# FubarinoMini_v11.net
KiCad netlist of a schematic drawn in EAGLE
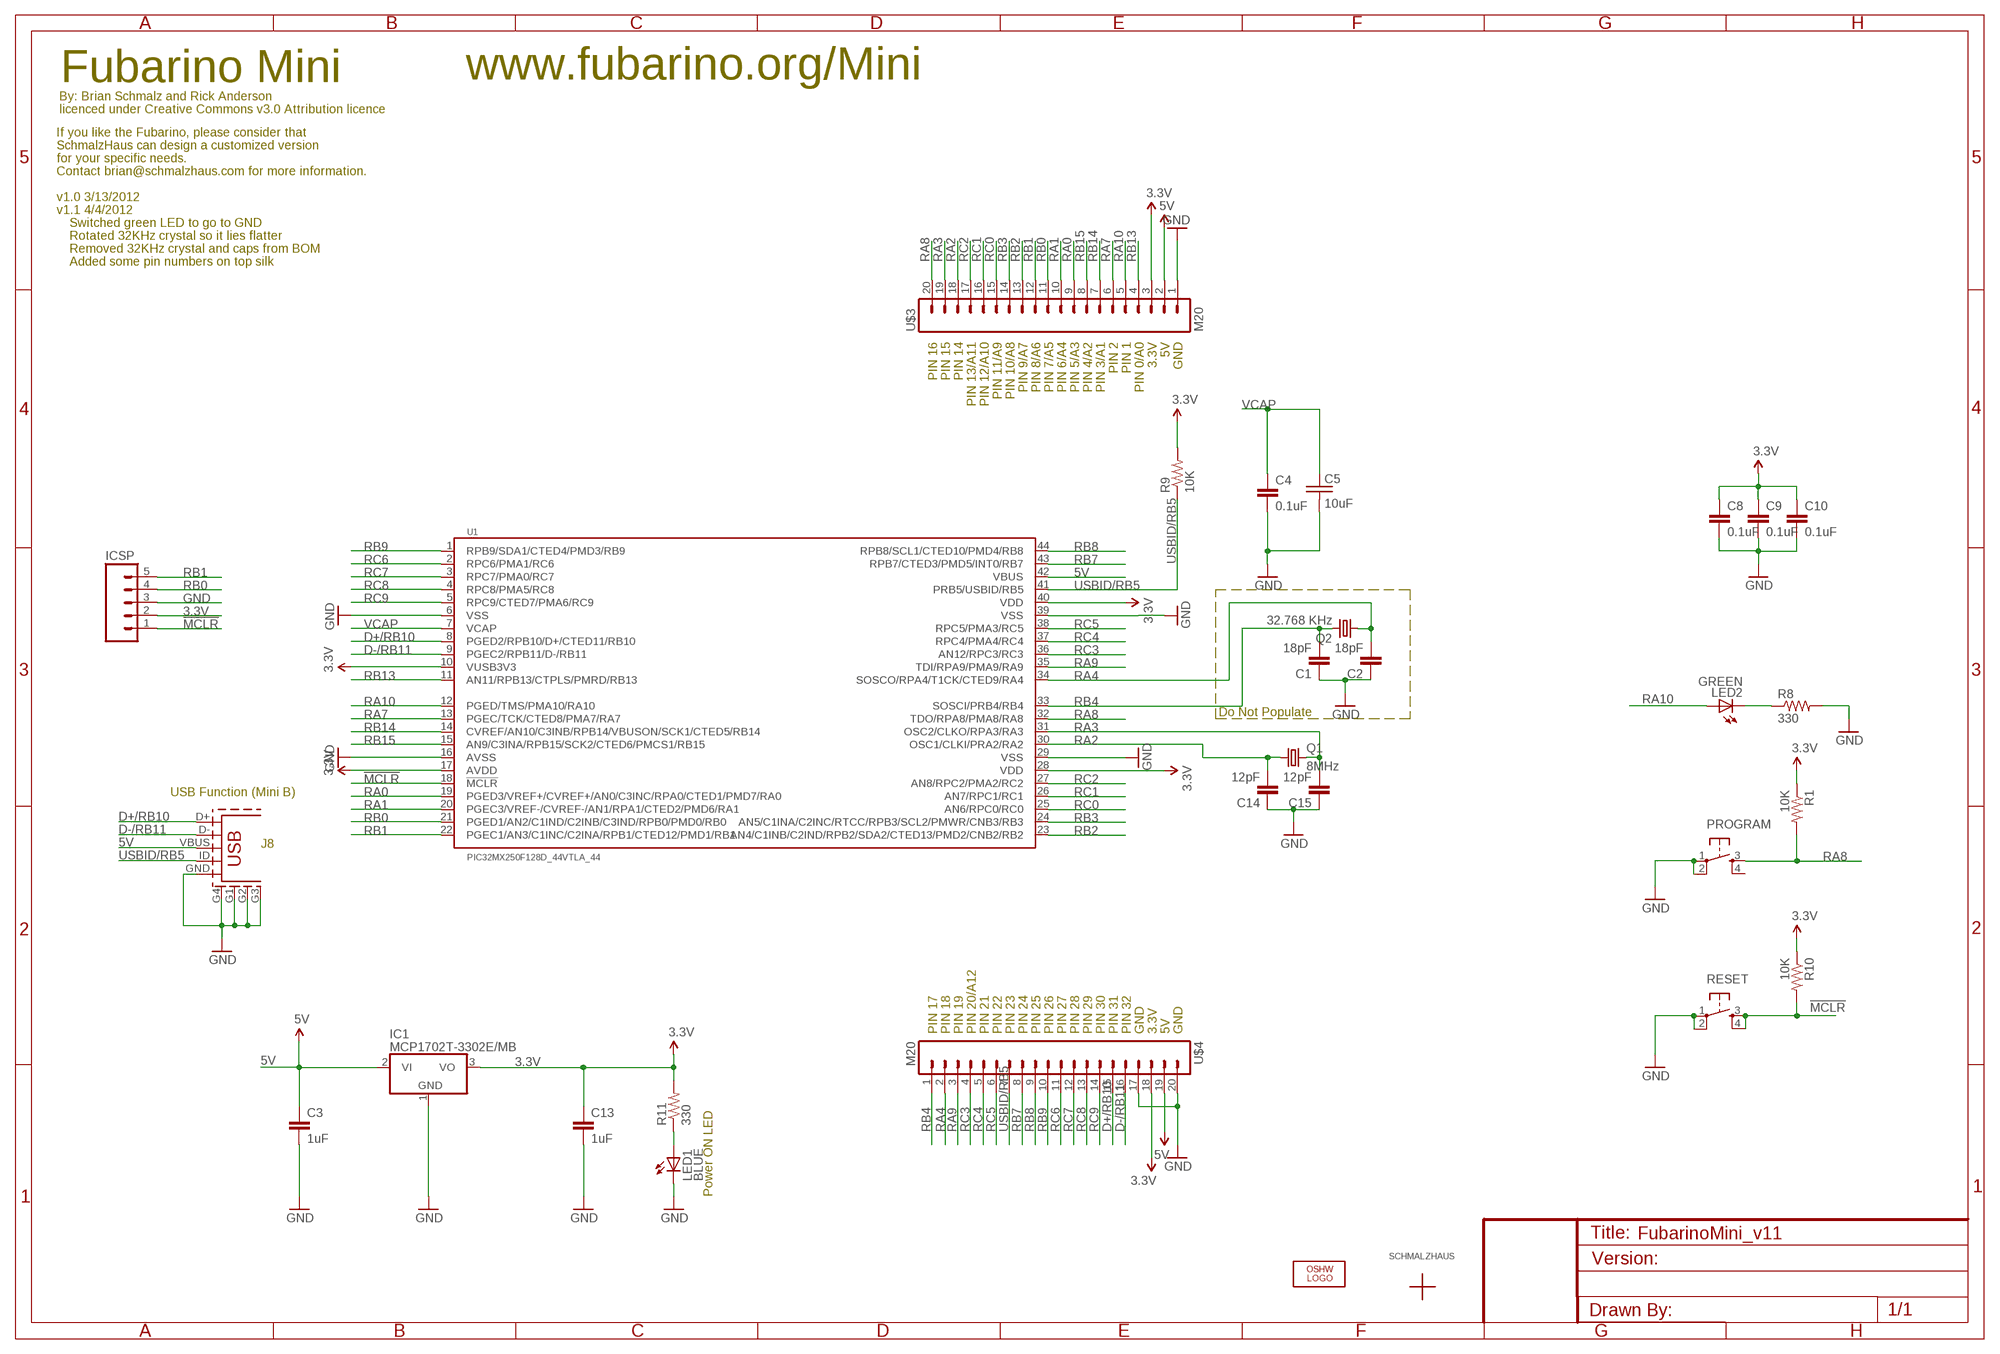
[diagram p0: schematic, sheet 1]

(export (version "E")
  (design (tool "Eeschema 10.0.6"))
  (components
    (comp (ref "C1")
      (value "18pF")
      (footprint "eagle-import:0603-CAP")
      (libsource (lib "eagle-import") (part "CAP0603-CAP"))
    )
    (comp (ref "C2")
      (value "18pF")
      (footprint "eagle-import:0603-CAP")
      (libsource (lib "eagle-import") (part "CAP0603-CAP"))
    )
    (comp (ref "C3")
      (value "1uF")
      (footprint "eagle-import:0603-CAP")
      (libsource (lib "eagle-import") (part "CAP0603-CAP"))
    )
    (comp (ref "C4")
      (value "0.1uF")
      (footprint "eagle-import:0603-CAP")
      (libsource (lib "eagle-import") (part "CAP0603-CAP"))
    )
    (comp (ref "C5")
      (value "10uF")
      (footprint "eagle-import:CAP_0805")
      (libsource (lib "eagle-import") (part "CAP0805"))
    )
    (comp (ref "C8")
      (value "0.1uF")
      (footprint "eagle-import:0603-CAP")
      (libsource (lib "eagle-import") (part "CAP0603-CAP"))
    )
    (comp (ref "C9")
      (value "0.1uF")
      (footprint "eagle-import:0603-CAP")
      (libsource (lib "eagle-import") (part "CAP0603-CAP"))
    )
    (comp (ref "C10")
      (value "0.1uF")
      (footprint "eagle-import:0603")
      (libsource (lib "eagle-import") (part "CAP0603"))
    )
    (comp (ref "C13")
      (value "1uF")
      (footprint "eagle-import:0603")
      (libsource (lib "eagle-import") (part "CAP0603"))
    )
    (comp (ref "C14")
      (value "12pF")
      (footprint "eagle-import:0603-CAP")
      (libsource (lib "eagle-import") (part "CAP0603-CAP"))
    )
    (comp (ref "C15")
      (value "12pF")
      (footprint "eagle-import:0603-CAP")
      (libsource (lib "eagle-import") (part "CAP0603-CAP"))
    )
    (comp (ref "IC1")
      (value "MCP1702T-3302E/MB")
      (footprint "eagle-import:SOT89")
      (libsource (lib "eagle-import") (part "MCP1703MB33"))
    )
    (comp (ref "ICSP")
      (value "M05NOSLILK")
      (footprint "eagle-import:1X05_NOSILK")
      (libsource (lib "eagle-import") (part "M05NOSLILK"))
    )
    (comp (ref "J8")
      (value "USB_5PIN")
      (footprint "eagle-import:USB-MINIB")
      (libsource (lib "eagle-import") (part "USB_5PIN"))
    )
    (comp (ref "LED1")
      (value "BLUE")
      (footprint "eagle-import:LED-0603")
      (libsource (lib "eagle-import") (part "LED0603"))
    )
    (comp (ref "LED2")
      (value "GREEN")
      (footprint "eagle-import:LED-0603")
      (libsource (lib "eagle-import") (part "LED0603"))
    )
    (comp (ref "LOGO1")
      (value "OSHW_LOGO_8MILX0070-NT")
      (footprint "eagle-import:OSHW_8X70_NOTEXT")
      (libsource (lib "eagle-import") (part "OSHW_LOGO_8MILX0070-NT"))
    )
    (comp (ref "PROGRAM")
      (value "TAC_SWITCHSND")
      (footprint "eagle-import:TACTILE_SWITCH_SMD")
      (libsource (lib "eagle-import") (part "TAC_SWITCHSND"))
    )
    (comp (ref "Q1")
      (value "8MHz")
      (footprint "eagle-import:NX5032_5MM_3.2MM_CRYSTAL")
      (libsource (lib "eagle-import") (part "CRYSTALNX5032"))
    )
    (comp (ref "Q2")
      (value "32.768 KHz")
      (footprint "eagle-import:TC26H")
      (libsource (lib "eagle-import") (part "CRYSTALTC26H"))
    )
    (comp (ref "R1")
      (value "10K")
      (footprint "eagle-import:0603-RES")
      (libsource (lib "eagle-import") (part "RESISTOR0603-RES"))
    )
    (comp (ref "R8")
      (value "330")
      (footprint "eagle-import:0603-RES")
      (libsource (lib "eagle-import") (part "RESISTOR0603-RES"))
    )
    (comp (ref "R9")
      (value "10K")
      (footprint "eagle-import:0603-RES")
      (libsource (lib "eagle-import") (part "RESISTOR0603-RES"))
    )
    (comp (ref "R10")
      (value "10K")
      (footprint "eagle-import:0603-RES")
      (libsource (lib "eagle-import") (part "RESISTOR0603-RES"))
    )
    (comp (ref "R11")
      (value "330")
      (footprint "eagle-import:0603-RES")
      (libsource (lib "eagle-import") (part "RESISTOR0603-RES"))
    )
    (comp (ref "RESET")
      (value "TAC_SWITCHSND")
      (footprint "eagle-import:TACTILE_SWITCH_SMD")
      (libsource (lib "eagle-import") (part "TAC_SWITCHSND"))
    )
    (comp (ref "U$1")
      (value "SCHMALZHAUSSCHMALZHAUS_SMALL")
      (footprint "eagle-import:SCHMALZHAUS_SMALL")
      (libsource (lib "eagle-import") (part "SCHMALZHAUSSCHMALZHAUS_SMALL"))
    )
    (comp (ref "U$3")
      (value "M20")
      (footprint "eagle-import:1X20_NO_PIN1")
      (libsource (lib "eagle-import") (part "M20"))
    )
    (comp (ref "U$4")
      (value "M20")
      (footprint "eagle-import:1X20_NO_PIN1")
      (libsource (lib "eagle-import") (part "M20"))
    )
    (comp (ref "U1")
      (value "PIC32MX250F128D_44VTLA_44")
      (footprint "eagle-import:VTLA_44")
      (libsource (lib "eagle-import") (part "PIC32MX2XX_44VLA_44"))
    )
  )
  (nets
    (net (code "1") (name "/D+{slash}RB10") (class "Default")
      (node (ref "J8") (pin "D+") (pinfunction "D+_D+") (pintype "bidirectional"))
      (node (ref "U$4") (pin "15") (pinfunction "15_15") (pintype "passive"))
      (node (ref "U1") (pin "8") (pinfunction "PGED2/RPB10/D+/CTED11/RB10_8") (pintype "bidirectional"))
    )
    (net (code "2") (name "/D-{slash}RB11") (class "Default")
      (node (ref "J8") (pin "D-") (pinfunction "D-_D-") (pintype "bidirectional"))
      (node (ref "U$4") (pin "16") (pinfunction "16_16") (pintype "passive"))
      (node (ref "U1") (pin "9") (pinfunction "PGEC2/RPB11/D-/RB11_9") (pintype "bidirectional"))
    )
    (net (code "3") (name "/RA0") (class "Default")
      (node (ref "U$3") (pin "9") (pinfunction "9_9") (pintype "passive"))
      (node (ref "U1") (pin "19") (pinfunction "PGED3/VREF+/CVREF+/AN0/C3INC/RPA0/CTED1/PMD7/RA0_19") (pintype "bidirectional"))
    )
    (net (code "4") (name "/RA1") (class "Default")
      (node (ref "U$3") (pin "10") (pinfunction "10_10") (pintype "passive"))
      (node (ref "U1") (pin "20") (pinfunction "PGEC3/VREF-/CVREF-/AN1/RPA1/CTED2/PMD6/RA1_20") (pintype "bidirectional"))
    )
    (net (code "5") (name "/RA2") (class "Default")
      (node (ref "C14") (pin "2") (pinfunction "2_2") (pintype "passive"))
      (node (ref "Q1") (pin "1") (pinfunction "1_1") (pintype "passive"))
      (node (ref "U$3") (pin "18") (pinfunction "18_18") (pintype "passive"))
      (node (ref "U1") (pin "30") (pinfunction "OSC1/CLKI/PRA2/RA2_30") (pintype "bidirectional"))
    )
    (net (code "6") (name "/RA3") (class "Default")
      (node (ref "C15") (pin "2") (pinfunction "2_2") (pintype "passive"))
      (node (ref "Q1") (pin "2") (pinfunction "2_2") (pintype "passive"))
      (node (ref "U$3") (pin "19") (pinfunction "19_19") (pintype "passive"))
      (node (ref "U1") (pin "31") (pinfunction "OSC2/CLKO/RPA3/RA3_31") (pintype "bidirectional"))
    )
    (net (code "7") (name "/RA4") (class "Default")
      (node (ref "C2") (pin "2") (pinfunction "2_2") (pintype "passive"))
      (node (ref "Q2") (pin "1") (pinfunction "1_1") (pintype "passive"))
      (node (ref "U$4") (pin "2") (pinfunction "2_2") (pintype "passive"))
      (node (ref "U1") (pin "34") (pinfunction "SOSCO/RPA4/T1CK/CTED9/RA4_34") (pintype "bidirectional"))
    )
    (net (code "8") (name "/RA7") (class "Default")
      (node (ref "U$3") (pin "6") (pinfunction "6_6") (pintype "passive"))
      (node (ref "U1") (pin "13") (pinfunction "PGEC/TCK/CTED8/PMA7/RA7_13") (pintype "bidirectional"))
    )
    (net (code "9") (name "/RA8") (class "Default")
      (node (ref "PROGRAM") (pin "3") (pinfunction "3_3") (pintype "passive"))
      (node (ref "R1") (pin "2") (pinfunction "2_2") (pintype "passive"))
      (node (ref "U$3") (pin "20") (pinfunction "20_20") (pintype "passive"))
      (node (ref "U1") (pin "32") (pinfunction "TDO/RPA8/PMA8/RA8_32") (pintype "bidirectional"))
    )
    (net (code "10") (name "/RA9") (class "Default")
      (node (ref "U$4") (pin "3") (pinfunction "3_3") (pintype "passive"))
      (node (ref "U1") (pin "35") (pinfunction "TDI/RPA9/PMA9/RA9_35") (pintype "bidirectional"))
    )
    (net (code "11") (name "/RA10") (class "Default")
      (node (ref "LED2") (pin "A") (pinfunction "A_A") (pintype "passive"))
      (node (ref "U$3") (pin "5") (pinfunction "5_5") (pintype "passive"))
      (node (ref "U1") (pin "12") (pinfunction "PGED/TMS/PMA10/RA10_12") (pintype "bidirectional"))
    )
    (net (code "12") (name "/RB0") (class "Default")
      (node (ref "ICSP") (pin "4") (pinfunction "4_4") (pintype "passive"))
      (node (ref "U$3") (pin "11") (pinfunction "11_11") (pintype "passive"))
      (node (ref "U1") (pin "21") (pinfunction "PGED1/AN2/C1IND/C2INB/C3IND/RPB0/PMD0/RB0_21") (pintype "bidirectional"))
    )
    (net (code "13") (name "/RB1") (class "Default")
      (node (ref "ICSP") (pin "5") (pinfunction "5_5") (pintype "passive"))
      (node (ref "U$3") (pin "12") (pinfunction "12_12") (pintype "passive"))
      (node (ref "U1") (pin "22") (pinfunction "PGEC1/AN3/C1INC/C2INA/RPB1/CTED12/PMD1/RB1_22") (pintype "bidirectional"))
    )
    (net (code "14") (name "/RB2") (class "Default")
      (node (ref "U$3") (pin "13") (pinfunction "13_13") (pintype "passive"))
      (node (ref "U1") (pin "23") (pinfunction "AN4/C1INB/C2IND/RPB2/SDA2/CTED13/PMD2/CNB2/RB2_23") (pintype "bidirectional"))
    )
    (net (code "15") (name "/RB3") (class "Default")
      (node (ref "U$3") (pin "14") (pinfunction "14_14") (pintype "passive"))
      (node (ref "U1") (pin "24") (pinfunction "AN5/C1INA/C2INC/RTCC/RPB3/SCL2/PMWR/CNB3/RB3_24") (pintype "bidirectional"))
    )
    (net (code "16") (name "/RB4") (class "Default")
      (node (ref "C1") (pin "2") (pinfunction "2_2") (pintype "passive"))
      (node (ref "Q2") (pin "2") (pinfunction "2_2") (pintype "passive"))
      (node (ref "U$4") (pin "1") (pinfunction "1_1") (pintype "passive"))
      (node (ref "U1") (pin "33") (pinfunction "SOSCI/PRB4/RB4_33") (pintype "bidirectional"))
    )
    (net (code "17") (name "/RB7") (class "Default")
      (node (ref "U$4") (pin "8") (pinfunction "8_8") (pintype "passive"))
      (node (ref "U1") (pin "43") (pinfunction "RPB7/CTED3/PMD5/INT0/RB7_43") (pintype "bidirectional"))
    )
    (net (code "18") (name "/RB8") (class "Default")
      (node (ref "U$4") (pin "9") (pinfunction "9_9") (pintype "passive"))
      (node (ref "U1") (pin "44") (pinfunction "RPB8/SCL1/CTED10/PMD4/RB8_44") (pintype "bidirectional"))
    )
    (net (code "19") (name "/RB9") (class "Default")
      (node (ref "U$4") (pin "10") (pinfunction "10_10") (pintype "passive"))
      (node (ref "U1") (pin "1") (pinfunction "RPB9/SDA1/CTED4/PMD3/RB9_1") (pintype "bidirectional"))
    )
    (net (code "20") (name "/RB13") (class "Default")
      (node (ref "U$3") (pin "4") (pinfunction "4_4") (pintype "passive"))
      (node (ref "U1") (pin "11") (pinfunction "AN11/RPB13/CTPLS/PMRD/RB13_11") (pintype "bidirectional"))
    )
    (net (code "21") (name "/RB14") (class "Default")
      (node (ref "U$3") (pin "7") (pinfunction "7_7") (pintype "passive"))
      (node (ref "U1") (pin "14") (pinfunction "CVREF/AN10/C3INB/RPB14/VBUSON/SCK1/CTED5/RB14_14") (pintype "bidirectional"))
    )
    (net (code "22") (name "/RB15") (class "Default")
      (node (ref "U$3") (pin "8") (pinfunction "8_8") (pintype "passive"))
      (node (ref "U1") (pin "15") (pinfunction "AN9/C3INA/RPB15/SCK2/CTED6/PMCS1/RB15_15") (pintype "bidirectional"))
    )
    (net (code "23") (name "/RC0") (class "Default")
      (node (ref "U$3") (pin "15") (pinfunction "15_15") (pintype "passive"))
      (node (ref "U1") (pin "25") (pinfunction "AN6/RPC0/RC0_25") (pintype "bidirectional"))
    )
    (net (code "24") (name "/RC1") (class "Default")
      (node (ref "U$3") (pin "16") (pinfunction "16_16") (pintype "passive"))
      (node (ref "U1") (pin "26") (pinfunction "AN7/RPC1/RC1_26") (pintype "bidirectional"))
    )
    (net (code "25") (name "/RC2") (class "Default")
      (node (ref "U$3") (pin "17") (pinfunction "17_17") (pintype "passive"))
      (node (ref "U1") (pin "27") (pinfunction "AN8/RPC2/PMA2/RC2_27") (pintype "bidirectional"))
    )
    (net (code "26") (name "/RC3") (class "Default")
      (node (ref "U$4") (pin "4") (pinfunction "4_4") (pintype "passive"))
      (node (ref "U1") (pin "36") (pinfunction "AN12/RPC3/RC3_36") (pintype "bidirectional"))
    )
    (net (code "27") (name "/RC4") (class "Default")
      (node (ref "U$4") (pin "5") (pinfunction "5_5") (pintype "passive"))
      (node (ref "U1") (pin "37") (pinfunction "RPC4/PMA4/RC4_37") (pintype "bidirectional"))
    )
    (net (code "28") (name "/RC5") (class "Default")
      (node (ref "U$4") (pin "6") (pinfunction "6_6") (pintype "passive"))
      (node (ref "U1") (pin "38") (pinfunction "RPC5/PMA3/RC5_38") (pintype "bidirectional"))
    )
    (net (code "29") (name "/RC6") (class "Default")
      (node (ref "U$4") (pin "11") (pinfunction "11_11") (pintype "passive"))
      (node (ref "U1") (pin "2") (pinfunction "RPC6/PMA1/RC6_2") (pintype "bidirectional"))
    )
    (net (code "30") (name "/RC7") (class "Default")
      (node (ref "U$4") (pin "12") (pinfunction "12_12") (pintype "passive"))
      (node (ref "U1") (pin "3") (pinfunction "RPC7/PMA0/RC7_3") (pintype "bidirectional"))
    )
    (net (code "31") (name "/RC8") (class "Default")
      (node (ref "U$4") (pin "13") (pinfunction "13_13") (pintype "passive"))
      (node (ref "U1") (pin "4") (pinfunction "RPC8/PMA5/RC8_4") (pintype "bidirectional"))
    )
    (net (code "32") (name "/RC9") (class "Default")
      (node (ref "U$4") (pin "14") (pinfunction "14_14") (pintype "passive"))
      (node (ref "U1") (pin "5") (pinfunction "RPC9/CTED7/PMA6/RC9_5") (pintype "bidirectional"))
    )
    (net (code "33") (name "/USBID{slash}RB5") (class "Default")
      (node (ref "J8") (pin "ID") (pinfunction "USB_ID_ID") (pintype "bidirectional"))
      (node (ref "R9") (pin "1") (pinfunction "1_1") (pintype "passive"))
      (node (ref "U$4") (pin "7") (pinfunction "7_7") (pintype "passive"))
      (node (ref "U1") (pin "41") (pinfunction "PRB5/USBID/RB5_41") (pintype "bidirectional"))
    )
    (net (code "34") (name "/VCAP") (class "Default")
      (node (ref "C4") (pin "1") (pinfunction "1_1") (pintype "passive"))
      (node (ref "C5") (pin "1") (pinfunction "1_1") (pintype "passive"))
      (node (ref "U1") (pin "7") (pinfunction "VCAP_7") (pintype "bidirectional"))
    )
    (net (code "35") (name "/~{MCLR}") (class "Default")
      (node (ref "ICSP") (pin "1") (pinfunction "1_1") (pintype "passive"))
      (node (ref "R10") (pin "2") (pinfunction "2_2") (pintype "passive"))
      (node (ref "RESET") (pin "3") (pinfunction "3_3") (pintype "passive"))
      (node (ref "RESET") (pin "4") (pinfunction "4_4") (pintype "passive"))
      (node (ref "U1") (pin "18") (pinfunction "~{MCLR}_18") (pintype "bidirectional"))
    )
    (net (code "36") (name "3.3V") (class "Default")
      (node (ref "C10") (pin "1") (pinfunction "1_1") (pintype "passive"))
      (node (ref "C13") (pin "1") (pinfunction "1_1") (pintype "passive"))
      (node (ref "C8") (pin "1") (pinfunction "1_1") (pintype "passive"))
      (node (ref "C9") (pin "1") (pinfunction "1_1") (pintype "passive"))
      (node (ref "IC1") (pin "3") (pinfunction "VO_3") (pintype "passive"))
      (node (ref "ICSP") (pin "2") (pinfunction "2_2") (pintype "passive"))
      (node (ref "R1") (pin "1") (pinfunction "1_1") (pintype "passive"))
      (node (ref "R10") (pin "1") (pinfunction "1_1") (pintype "passive"))
      (node (ref "R11") (pin "2") (pinfunction "2_2") (pintype "passive"))
      (node (ref "R9") (pin "2") (pinfunction "2_2") (pintype "passive"))
      (node (ref "U$3") (pin "3") (pinfunction "3_3") (pintype "passive"))
      (node (ref "U$4") (pin "18") (pinfunction "18_18") (pintype "passive"))
      (node (ref "U1") (pin "10") (pinfunction "VUSB3V3_10") (pintype "bidirectional"))
      (node (ref "U1") (pin "17") (pinfunction "AVDD_17") (pintype "bidirectional"))
      (node (ref "U1") (pin "28") (pinfunction "VDD_28") (pintype "bidirectional"))
      (node (ref "U1") (pin "40") (pinfunction "VDD_40") (pintype "bidirectional"))
    )
    (net (code "37") (name "5V") (class "Default")
      (node (ref "C3") (pin "1") (pinfunction "1_1") (pintype "passive"))
      (node (ref "IC1") (pin "2") (pinfunction "VI_2") (pintype "input"))
      (node (ref "IC1") (pin "2@1") (pinfunction "VI1_2@1") (pintype "input"))
      (node (ref "J8") (pin "VBUS") (pinfunction "VBUS_VBUS") (pintype "bidirectional"))
      (node (ref "U$3") (pin "2") (pinfunction "2_2") (pintype "passive"))
      (node (ref "U$4") (pin "19") (pinfunction "19_19") (pintype "passive"))
      (node (ref "U1") (pin "42") (pinfunction "VBUS_42") (pintype "bidirectional"))
    )
    (net (code "38") (name "GND") (class "Default")
      (node (ref "C1") (pin "1") (pinfunction "1_1") (pintype "passive"))
      (node (ref "C10") (pin "2") (pinfunction "2_2") (pintype "passive"))
      (node (ref "C13") (pin "2") (pinfunction "2_2") (pintype "passive"))
      (node (ref "C14") (pin "1") (pinfunction "1_1") (pintype "passive"))
      (node (ref "C15") (pin "1") (pinfunction "1_1") (pintype "passive"))
      (node (ref "C2") (pin "1") (pinfunction "1_1") (pintype "passive"))
      (node (ref "C3") (pin "2") (pinfunction "2_2") (pintype "passive"))
      (node (ref "C4") (pin "2") (pinfunction "2_2") (pintype "passive"))
      (node (ref "C5") (pin "2") (pinfunction "2_2") (pintype "passive"))
      (node (ref "C8") (pin "2") (pinfunction "2_2") (pintype "passive"))
      (node (ref "C9") (pin "2") (pinfunction "2_2") (pintype "passive"))
      (node (ref "IC1") (pin "1") (pinfunction "GND_1") (pintype "passive"))
      (node (ref "ICSP") (pin "3") (pinfunction "3_3") (pintype "passive"))
      (node (ref "J8") (pin "G1") (pinfunction "P$1_G1") (pintype "bidirectional"))
      (node (ref "J8") (pin "G2") (pinfunction "P$2_G2") (pintype "bidirectional"))
      (node (ref "J8") (pin "G3") (pinfunction "P$3_G3") (pintype "bidirectional"))
      (node (ref "J8") (pin "G4") (pinfunction "SHIELD_G4") (pintype "bidirectional"))
      (node (ref "J8") (pin "GND") (pinfunction "GND_GND") (pintype "bidirectional"))
      (node (ref "LED1") (pin "C") (pinfunction "C_C") (pintype "passive"))
      (node (ref "PROGRAM") (pin "1") (pinfunction "1_1") (pintype "passive"))
      (node (ref "PROGRAM") (pin "2") (pinfunction "2_2") (pintype "passive"))
      (node (ref "R8") (pin "2") (pinfunction "2_2") (pintype "passive"))
      (node (ref "RESET") (pin "1") (pinfunction "1_1") (pintype "passive"))
      (node (ref "RESET") (pin "2") (pinfunction "2_2") (pintype "passive"))
      (node (ref "U$3") (pin "1") (pinfunction "1_1") (pintype "passive"))
      (node (ref "U$4") (pin "17") (pinfunction "17_17") (pintype "passive"))
      (node (ref "U$4") (pin "20") (pinfunction "20_20") (pintype "passive"))
      (node (ref "U1") (pin "16") (pinfunction "AVSS_16") (pintype "bidirectional"))
      (node (ref "U1") (pin "29") (pinfunction "VSS_29") (pintype "bidirectional"))
      (node (ref "U1") (pin "39") (pinfunction "VSS_39") (pintype "bidirectional"))
      (node (ref "U1") (pin "6") (pinfunction "VSS_6") (pintype "bidirectional"))
    )
    (net (code "39") (name "Net-(LED1-PadA)") (class "Default")
      (node (ref "LED1") (pin "A") (pinfunction "A_A") (pintype "passive"))
      (node (ref "R11") (pin "1") (pinfunction "1_1") (pintype "passive"))
    )
    (net (code "40") (name "Net-(LED2-PadC)") (class "Default")
      (node (ref "LED2") (pin "C") (pinfunction "C_C") (pintype "passive"))
      (node (ref "R8") (pin "1") (pinfunction "1_1") (pintype "passive"))
    )
    (net (code "41") (name "unconnected-(PROGRAM-Pad4)") (class "Default")
      (node (ref "PROGRAM") (pin "4") (pinfunction "4_4") (pintype "passive"))
    )
  )
)
